# Arduino-Teensy-v44_PLUS_ESP-12E_4LAYER.net
KiCad netlist of a schematic drawn in EAGLE
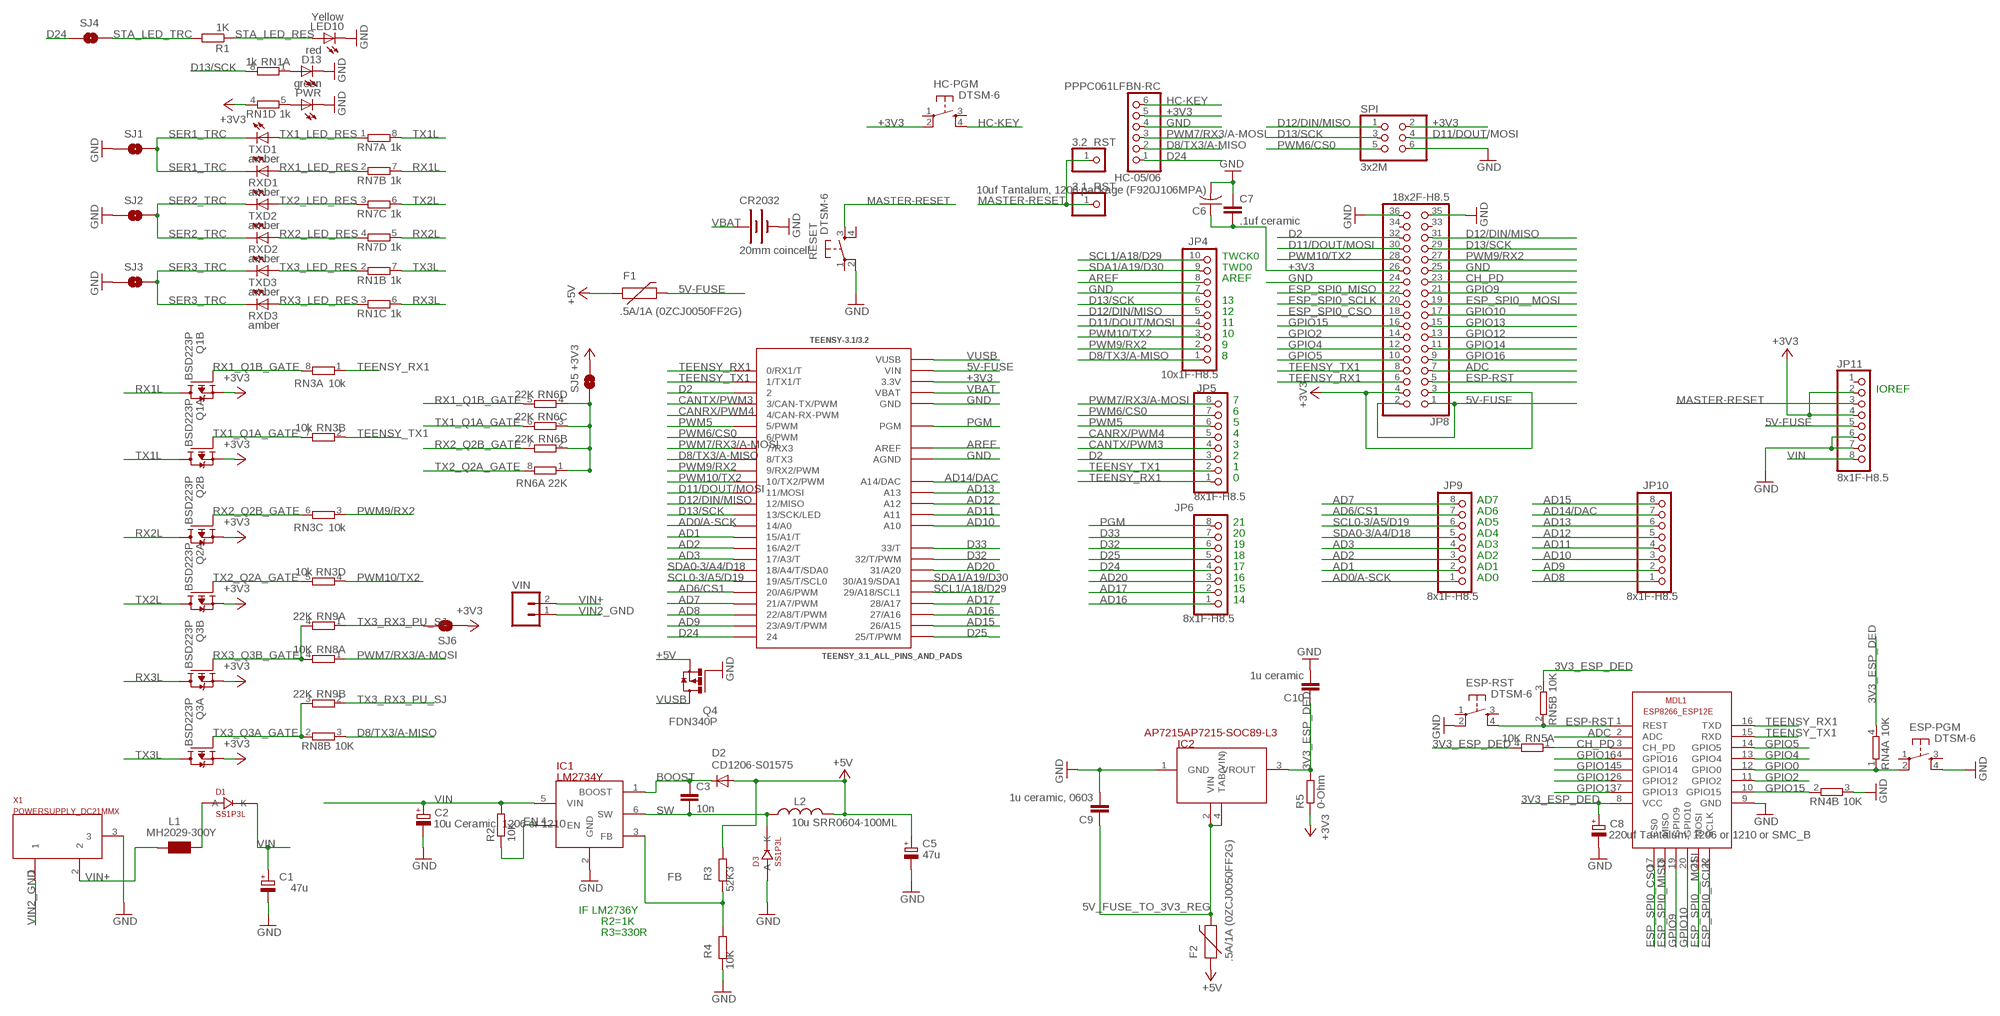
[diagram p0: schematic, sheet 1]

(export (version "E")
  (design (tool "Eeschema 10.0.6"))
  (components
    (comp (ref "3.1_RST")
      (value "PINHD-1X1CB")
      (footprint "eagle-import:1X01-CLEANBIG")
      (libsource (lib "eagle-import") (part "PINHD-1X1CB"))
    )
    (comp (ref "3.2_RST")
      (value "PINHD-1X1CB")
      (footprint "eagle-import:1X01-CLEANBIG")
      (libsource (lib "eagle-import") (part "PINHD-1X1CB"))
    )
    (comp (ref "C1")
      (value "47u")
      (footprint "eagle-import:PANASONIC_D")
      (libsource (lib "eagle-import") (part "CPOL-EUD"))
    )
    (comp (ref "C2")
      (value "10u Ceramic, 1206 or 1210")
      (footprint "eagle-import:SMC_B")
      (libsource (lib "eagle-import") (part "CPOL-EUSMCB"))
    )
    (comp (ref "C3")
      (value "10n")
      (footprint "eagle-import:C0603-ROUND")
      (libsource (lib "eagle-import") (part "C-EUC0603"))
    )
    (comp (ref "C5")
      (value "47u")
      (footprint "eagle-import:PANASONIC_D")
      (libsource (lib "eagle-import") (part "CPOL-EUD"))
    )
    (comp (ref "C6")
      (value "10uf Tantalum, 1206 package (F920J106MPA)")
      (footprint "eagle-import:C0805")
      (libsource (lib "eagle-import") (part "C-USC0805"))
    )
    (comp (ref "C7")
      (value ".1uf ceramic")
      (footprint "eagle-import:C0603-ROUND")
      (libsource (lib "eagle-import") (part "C-EUC0603"))
    )
    (comp (ref "C8")
      (value "220uf Tantalum, 1206 or 1210 or SMC_B")
      (footprint "eagle-import:SMC_B")
      (libsource (lib "eagle-import") (part "CPOL-EUSMCB"))
    )
    (comp (ref "C9")
      (value "1u ceramic, 0603")
      (footprint "eagle-import:C0603-ROUND")
      (libsource (lib "eagle-import") (part "C-EUC0603"))
    )
    (comp (ref "C10")
      (value "1u ceramic")
      (footprint "eagle-import:C0603-ROUND")
      (libsource (lib "eagle-import") (part "C-EUC0603"))
    )
    (comp (ref "CR2032")
      (value "20mm coincell")
      (footprint "eagle-import:BATTCON_20MM_4LEGS")
      (libsource (lib "eagle-import") (part "BATTERY20MM_4LEGS"))
    )
    (comp (ref "D1")
      (value "SS1P3L")
      (footprint "eagle-import:DO220AAL")
      (libsource (lib "eagle-import") (part "SS1P3L"))
    )
    (comp (ref "D2")
      (value "CD1206-S01575")
      (footprint "eagle-import:MINIMELF")
      (libsource (lib "eagle-import") (part "DIODE-MINIMELF"))
    )
    (comp (ref "D3")
      (value "SS1P3L")
      (footprint "eagle-import:DO220AAL")
      (libsource (lib "eagle-import") (part "SS1P3L"))
    )
    (comp (ref "D13")
      (value "red")
      (footprint "eagle-import:CHIPLED_0805")
      (libsource (lib "eagle-import") (part "LEDCHIPLED_0805"))
    )
    (comp (ref "ESP-PGM")
      (value "DTSM-6")
      (footprint "eagle-import:DTSM-6")
      (libsource (lib "eagle-import") (part "DTSM-6"))
    )
    (comp (ref "ESP-RST")
      (value "DTSM-6")
      (footprint "eagle-import:DTSM-6")
      (libsource (lib "eagle-import") (part "DTSM-6"))
    )
    (comp (ref "F1")
      (value ".5A/1A (0ZCJ0050FF2G)")
      (footprint "eagle-import:PTC-1206")
      (libsource (lib "eagle-import") (part "PTCSMD"))
    )
    (comp (ref "F2")
      (value ".5A/1A (0ZCJ0050FF2G)")
      (footprint "eagle-import:PTC-1206")
      (libsource (lib "eagle-import") (part "PTCSMD"))
    )
    (comp (ref "HC-05/06")
      (value "PPPC061LFBN-RC")
      (footprint "eagle-import:1X06")
      (libsource (lib "eagle-import") (part "PINHD-1X6"))
    )
    (comp (ref "HC-PGM")
      (value "DTSM-6")
      (footprint "eagle-import:DTSM-6")
      (libsource (lib "eagle-import") (part "DTSM-6"))
    )
    (comp (ref "IC1")
      (value "LM2734Y")
      (footprint "eagle-import:SOT23-6")
      (libsource (lib "eagle-import") (part "LM2736Y"))
    )
    (comp (ref "IC2")
      (value "AP7215AP7215-SOC89-L3")
      (footprint "eagle-import:SOC89-L3")
      (libsource (lib "eagle-import") (part "AP7215AP7215-SOC89-L3"))
    )
    (comp (ref "JP4")
      (value "10x1F-H8.5")
      (footprint "eagle-import:1X10")
      (libsource (lib "eagle-import") (part "PINHD-1X10"))
    )
    (comp (ref "JP5")
      (value "8x1F-H8.5")
      (footprint "eagle-import:1X08")
      (libsource (lib "eagle-import") (part "PINHD-1X8"))
    )
    (comp (ref "JP6")
      (value "8x1F-H8.5")
      (footprint "eagle-import:1X08")
      (libsource (lib "eagle-import") (part "PINHD-1X8"))
    )
    (comp (ref "JP8")
      (value "18x2F-H8.5")
      (footprint "eagle-import:2X18")
      (libsource (lib "eagle-import") (part "PINHD-2X18"))
    )
    (comp (ref "JP9")
      (value "8x1F-H8.5")
      (footprint "eagle-import:1X08")
      (libsource (lib "eagle-import") (part "PINHD-1X8"))
    )
    (comp (ref "JP10")
      (value "8x1F-H8.5")
      (footprint "eagle-import:1X08")
      (libsource (lib "eagle-import") (part "PINHD-1X8"))
    )
    (comp (ref "JP11")
      (value "8x1F-H8.5")
      (footprint "eagle-import:1X08")
      (libsource (lib "eagle-import") (part "PINHD-1X8"))
    )
    (comp (ref "L1")
      (value "MH2029-300Y")
      (footprint "eagle-import:0805")
      (libsource (lib "eagle-import") (part "WE-CBF_0805"))
    )
    (comp (ref "L2")
      (value "10u SRR0604-100ML")
      (footprint "eagle-import:SRR0604")
      (libsource (lib "eagle-import") (part "L-USSRR0604"))
    )
    (comp (ref "LED10")
      (value "Yellow")
      (footprint "eagle-import:CHIPLED_0805")
      (libsource (lib "eagle-import") (part "LEDCHIPLED_0805"))
    )
    (comp (ref "MDL1")
      (value "ESP8266-12E)")
      (footprint "eagle-import:ESP8266-ESP12E")
      (libsource (lib "eagle-import") (part "ESP8266-12EESP8266-ESP12E"))
    )
    (comp (ref "PWR")
      (value "green")
      (footprint "eagle-import:CHIPLED_0805")
      (libsource (lib "eagle-import") (part "LEDCHIPLED_0805"))
    )
    (comp (ref "Q1")
      (value "BSD223P")
      (footprint "eagle-import:SOT363_INFINEON")
      (libsource (lib "eagle-import") (part "BSD223P"))
    )
    (comp (ref "Q2")
      (value "BSD223P")
      (footprint "eagle-import:SOT363_INFINEON")
      (libsource (lib "eagle-import") (part "BSD223P"))
    )
    (comp (ref "Q3")
      (value "BSD223P")
      (footprint "eagle-import:SOT363_INFINEON")
      (libsource (lib "eagle-import") (part "BSD223P"))
    )
    (comp (ref "Q4")
      (value "FDN340P")
      (footprint "eagle-import:SUPER-SOT3")
      (libsource (lib "eagle-import") (part "FDN360P"))
    )
    (comp (ref "R1")
      (value "1K")
      (footprint "eagle-import:R0603")
      (libsource (lib "eagle-import") (part "rcl_R-EU_R0603"))
    )
    (comp (ref "R2")
      (value "10K")
      (footprint "eagle-import:R0603")
      (libsource (lib "eagle-import") (part "rcl_R-EU_R0603"))
    )
    (comp (ref "R3")
      (value "52K3")
      (footprint "eagle-import:R0603-ROUND")
      (libsource (lib "eagle-import") (part "R-EU_0603-RND"))
    )
    (comp (ref "R4")
      (value "10K")
      (footprint "eagle-import:R0603-ROUND")
      (libsource (lib "eagle-import") (part "R-EU_0603-RND"))
    )
    (comp (ref "R5")
      (value "0-Ohm")
      (footprint "eagle-import:R0603")
      (libsource (lib "eagle-import") (part "rcl_R-EU_R0603"))
    )
    (comp (ref "RESET")
      (value "DTSM-6")
      (footprint "eagle-import:DTSM-6")
      (libsource (lib "eagle-import") (part "DTSM-6"))
    )
    (comp (ref "RN1")
      (value "1k")
      (footprint "eagle-import:CAT16")
      (libsource (lib "eagle-import") (part "4R-NCAT16"))
    )
    (comp (ref "RN3")
      (value "10k")
      (footprint "eagle-import:CAT16")
      (libsource (lib "eagle-import") (part "4R-NCAT16"))
    )
    (comp (ref "RN4")
      (value "10K")
      (footprint "eagle-import:EXB34V")
      (libsource (lib "eagle-import") (part "2R-NEXB34V"))
    )
    (comp (ref "RN5")
      (value "10K")
      (footprint "eagle-import:EXB34V")
      (libsource (lib "eagle-import") (part "2R-NEXB34V"))
    )
    (comp (ref "RN6")
      (value "22K")
      (footprint "eagle-import:CAT16")
      (libsource (lib "eagle-import") (part "4R-NCAT16"))
    )
    (comp (ref "RN7")
      (value "1k")
      (footprint "eagle-import:CAT16")
      (libsource (lib "eagle-import") (part "4R-NCAT16"))
    )
    (comp (ref "RN8")
      (value "10K")
      (footprint "eagle-import:EXB34V")
      (libsource (lib "eagle-import") (part "2R-NEXB34V"))
    )
    (comp (ref "RN9")
      (value "22K")
      (footprint "eagle-import:EXB34V")
      (libsource (lib "eagle-import") (part "2R-NEXB34V"))
    )
    (comp (ref "RXD1")
      (value "amber")
      (footprint "eagle-import:CHIPLED_0805")
      (libsource (lib "eagle-import") (part "LEDCHIPLED_0805"))
    )
    (comp (ref "RXD2")
      (value "amber")
      (footprint "eagle-import:CHIPLED_0805")
      (libsource (lib "eagle-import") (part "LEDCHIPLED_0805"))
    )
    (comp (ref "RXD3")
      (value "amber")
      (footprint "eagle-import:CHIPLED_0805")
      (libsource (lib "eagle-import") (part "LEDCHIPLED_0805"))
    )
    (comp (ref "SJ1")
      (value "SOLDERJUMPERTRACE")
      (footprint "eagle-import:SJ_2S-TRACE")
      (libsource (lib "eagle-import") (part "SOLDERJUMPERTRACE"))
    )
    (comp (ref "SJ2")
      (value "SOLDERJUMPERTRACE")
      (footprint "eagle-import:SJ_2S-TRACE")
      (libsource (lib "eagle-import") (part "SOLDERJUMPERTRACE"))
    )
    (comp (ref "SJ3")
      (value "SOLDERJUMPERTRACE")
      (footprint "eagle-import:SJ_2S-TRACE")
      (libsource (lib "eagle-import") (part "SOLDERJUMPERTRACE"))
    )
    (comp (ref "SJ4")
      (value "SOLDERJUMPERTRACE")
      (footprint "eagle-import:SJ_2S-TRACE")
      (libsource (lib "eagle-import") (part "SOLDERJUMPERTRACE"))
    )
    (comp (ref "SJ5")
      (value "SOLDERJUMPERTRACE")
      (footprint "eagle-import:SJ_2S-TRACE")
      (libsource (lib "eagle-import") (part "SOLDERJUMPERTRACE"))
    )
    (comp (ref "SJ6")
      (value "SOLDERJUMPERTRACE")
      (footprint "eagle-import:SJ_2S-TRACE")
      (libsource (lib "eagle-import") (part "SOLDERJUMPERTRACE"))
    )
    (comp (ref "SPI")
      (value "3x2M")
      (footprint "eagle-import:2X03")
      (libsource (lib "eagle-import") (part "PINHD-2X3"))
    )
    (comp (ref "TEENSY-3.1/3.2")
      (value "TEENSY_3.1_ALL_PINS_AND_PADS")
      (footprint "eagle-import:TEENSY3_ALL_PINS_&_PADS")
      (libsource (lib "eagle-import") (part "TEENSY_3.1_ALL_PINS_AND_PADS"))
    )
    (comp (ref "TXD1")
      (value "amber")
      (footprint "eagle-import:CHIPLED_0805")
      (libsource (lib "eagle-import") (part "LEDCHIPLED_0805"))
    )
    (comp (ref "TXD2")
      (value "amber")
      (footprint "eagle-import:CHIPLED_0805")
      (libsource (lib "eagle-import") (part "LEDCHIPLED_0805"))
    )
    (comp (ref "TXD3")
      (value "amber")
      (footprint "eagle-import:CHIPLED_0805")
      (libsource (lib "eagle-import") (part "LEDCHIPLED_0805"))
    )
    (comp (ref "VIN")
      (value "M02LOCK_LONGPADS")
      (footprint "eagle-import:1X02_LOCK_LONGPADS")
      (libsource (lib "eagle-import") (part "M02LOCK_LONGPADS"))
    )
    (comp (ref "X1")
      (value "POWERSUPPLY_DC21MMX")
      (footprint "eagle-import:POWERSUPPLY_DC-21MM")
      (libsource (lib "eagle-import") (part "POWERSUPPLY_DC21MMX"))
    )
  )
  (nets
    (net (code "1") (name "+3V3") (class "Default")
      (node (ref "C6") (pin "1") (pinfunction "1_1") (pintype "passive"))
      (node (ref "C7") (pin "2") (pinfunction "2_2") (pintype "passive"))
      (node (ref "HC-05/06") (pin "5") (pinfunction "5_5") (pintype "passive"))
      (node (ref "HC-PGM") (pin "2") (pinfunction "2_2") (pintype "passive"))
      (node (ref "JP11") (pin "2") (pinfunction "2_2") (pintype "passive"))
      (node (ref "JP11") (pin "4") (pinfunction "4_4") (pintype "passive"))
      (node (ref "JP8") (pin "26") (pinfunction "26_26") (pintype "passive"))
      (node (ref "JP8") (pin "3") (pinfunction "3_3") (pintype "passive"))
      (node (ref "JP8") (pin "4") (pinfunction "4_4") (pintype "passive"))
      (node (ref "Q1") (pin "1") (pinfunction "S_1") (pintype "passive"))
      (node (ref "Q1") (pin "4") (pinfunction "S_4") (pintype "passive"))
      (node (ref "Q2") (pin "1") (pinfunction "S_1") (pintype "passive"))
      (node (ref "Q2") (pin "4") (pinfunction "S_4") (pintype "passive"))
      (node (ref "Q3") (pin "1") (pinfunction "S_1") (pintype "passive"))
      (node (ref "Q3") (pin "4") (pinfunction "S_4") (pintype "passive"))
      (node (ref "R5") (pin "1") (pinfunction "1_1") (pintype "passive"))
      (node (ref "RN1") (pin "4") (pinfunction "1_4") (pintype "passive"))
      (node (ref "SJ5") (pin "2") (pinfunction "2_2") (pintype "passive"))
      (node (ref "SJ6") (pin "1") (pinfunction "1_1") (pintype "passive"))
      (node (ref "SPI") (pin "2") (pinfunction "2_2") (pintype "passive"))
      (node (ref "TEENSY-3.1/3.2") (pin "3.3V") (pinfunction "3.3V_3.3V") (pintype "power_in"))
      (node (ref "TEENSY-3.1/3.2") (pin "3.3V1") (pinfunction "3.3V_3.3V1") (pintype "power_in"))
      (node (ref "TEENSY-3.1/3.2") (pin "3.3V2") (pinfunction "3.3V_3.3V2") (pintype "power_in"))
    )
    (net (code "2") (name "+5V") (class "Default")
      (node (ref "C5") (pin "+") (pinfunction "+_+") (pintype "passive"))
      (node (ref "D2") (pin "A") (pinfunction "A_A") (pintype "passive"))
      (node (ref "F1") (pin "1") (pinfunction "1_1") (pintype "bidirectional"))
      (node (ref "F2") (pin "1") (pinfunction "1_1") (pintype "bidirectional"))
      (node (ref "L2") (pin "P$2") (pinfunction "2_P$2") (pintype "passive"))
      (node (ref "Q4") (pin "2") (pinfunction "S_2") (pintype "passive"))
      (node (ref "R3") (pin "1") (pinfunction "1_1") (pintype "passive"))
    )
    (net (code "3") (name "/3V3_ESP_DED") (class "Default")
      (node (ref "C10") (pin "1") (pinfunction "1_1") (pintype "passive"))
      (node (ref "C8") (pin "+") (pinfunction "+_+") (pintype "passive"))
      (node (ref "IC2") (pin "3") (pinfunction "VROUT_3") (pintype "output"))
      (node (ref "MDL1") (pin "8") (pinfunction "VCC_8") (pintype "bidirectional"))
      (node (ref "R5") (pin "2") (pinfunction "2_2") (pintype "passive"))
      (node (ref "RN4") (pin "4") (pinfunction "2_4") (pintype "passive"))
      (node (ref "RN5") (pin "3") (pinfunction "2_3") (pintype "passive"))
      (node (ref "RN5") (pin "4") (pinfunction "2_4") (pintype "passive"))
    )
    (net (code "4") (name "/5V-FUSE") (class "Default")
      (node (ref "F1") (pin "2") (pinfunction "2_2") (pintype "bidirectional"))
      (node (ref "JP11") (pin "5") (pinfunction "5_5") (pintype "passive"))
      (node (ref "JP8") (pin "1") (pinfunction "1_1") (pintype "passive"))
      (node (ref "JP8") (pin "2") (pinfunction "2_2") (pintype "passive"))
      (node (ref "TEENSY-3.1/3.2") (pin "VIN") (pinfunction "VIN_VIN") (pintype "power_in"))
    )
    (net (code "5") (name "/5V_FUSE_TO_3V3_REG") (class "Default")
      (node (ref "C9") (pin "1") (pinfunction "1_1") (pintype "passive"))
      (node (ref "F2") (pin "2") (pinfunction "2_2") (pintype "bidirectional"))
      (node (ref "IC2") (pin "2") (pinfunction "VIN_2") (pintype "input"))
      (node (ref "IC2") (pin "4") (pinfunction "TAB(VIN)_4") (pintype "input"))
    )
    (net (code "6") (name "/AD0{slash}A-SCK") (class "Default")
      (node (ref "JP9") (pin "1") (pinfunction "1_1") (pintype "passive"))
      (node (ref "TEENSY-3.1/3.2") (pin "14/A0") (pinfunction "14/A0_14/A0") (pintype "bidirectional"))
    )
    (net (code "7") (name "/AD1") (class "Default")
      (node (ref "JP9") (pin "2") (pinfunction "2_2") (pintype "passive"))
      (node (ref "TEENSY-3.1/3.2") (pin "15/A1") (pinfunction "15/A1/T_15/A1") (pintype "bidirectional"))
    )
    (net (code "8") (name "/AD2") (class "Default")
      (node (ref "JP9") (pin "3") (pinfunction "3_3") (pintype "passive"))
      (node (ref "TEENSY-3.1/3.2") (pin "16/A2") (pinfunction "16/A2/T_16/A2") (pintype "bidirectional"))
    )
    (net (code "9") (name "/AD3") (class "Default")
      (node (ref "JP9") (pin "4") (pinfunction "4_4") (pintype "passive"))
      (node (ref "TEENSY-3.1/3.2") (pin "17/A3") (pinfunction "17/A3/T_17/A3") (pintype "bidirectional"))
    )
    (net (code "10") (name "/AD6{slash}CS1") (class "Default")
      (node (ref "JP9") (pin "7") (pinfunction "7_7") (pintype "passive"))
      (node (ref "TEENSY-3.1/3.2") (pin "20/A6") (pinfunction "20/A6/PWM_20/A6") (pintype "bidirectional"))
    )
    (net (code "11") (name "/AD7") (class "Default")
      (node (ref "JP9") (pin "8") (pinfunction "8_8") (pintype "passive"))
      (node (ref "TEENSY-3.1/3.2") (pin "21/A7") (pinfunction "21/A7/PWM_21/A7") (pintype "bidirectional"))
    )
    (net (code "12") (name "/AD8") (class "Default")
      (node (ref "JP10") (pin "1") (pinfunction "1_1") (pintype "passive"))
      (node (ref "TEENSY-3.1/3.2") (pin "22/A8") (pinfunction "22/A8/T/PWM_22/A8") (pintype "bidirectional"))
    )
    (net (code "13") (name "/AD9") (class "Default")
      (node (ref "JP10") (pin "2") (pinfunction "2_2") (pintype "passive"))
      (node (ref "TEENSY-3.1/3.2") (pin "23/A9") (pinfunction "23/A9/T/PWM_23/A9") (pintype "bidirectional"))
    )
    (net (code "14") (name "/AD10") (class "Default")
      (node (ref "JP10") (pin "3") (pinfunction "3_3") (pintype "passive"))
      (node (ref "TEENSY-3.1/3.2") (pin "A10") (pinfunction "A10_A10") (pintype "bidirectional"))
    )
    (net (code "15") (name "/AD11") (class "Default")
      (node (ref "JP10") (pin "4") (pinfunction "4_4") (pintype "passive"))
      (node (ref "TEENSY-3.1/3.2") (pin "A11") (pinfunction "A11_A11") (pintype "bidirectional"))
    )
    (net (code "16") (name "/AD12") (class "Default")
      (node (ref "JP10") (pin "5") (pinfunction "5_5") (pintype "passive"))
      (node (ref "TEENSY-3.1/3.2") (pin "A12") (pinfunction "A12_A12") (pintype "bidirectional"))
    )
    (net (code "17") (name "/AD13") (class "Default")
      (node (ref "JP10") (pin "6") (pinfunction "6_6") (pintype "passive"))
      (node (ref "TEENSY-3.1/3.2") (pin "A13") (pinfunction "A13_A13") (pintype "bidirectional"))
    )
    (net (code "18") (name "/AD14{slash}DAC") (class "Default")
      (node (ref "JP10") (pin "7") (pinfunction "7_7") (pintype "passive"))
      (node (ref "TEENSY-3.1/3.2") (pin "RESET/DAC") (pinfunction "A14/DAC_RESET/DAC") (pintype "bidirectional"))
    )
    (net (code "19") (name "/AD15") (class "Default")
      (node (ref "JP10") (pin "8") (pinfunction "8_8") (pintype "passive"))
      (node (ref "TEENSY-3.1/3.2") (pin "26") (pinfunction "26/A15_26") (pintype "bidirectional"))
    )
    (net (code "20") (name "/AD16") (class "Default")
      (node (ref "JP6") (pin "1") (pinfunction "1_1") (pintype "passive"))
      (node (ref "TEENSY-3.1/3.2") (pin "27") (pinfunction "27/A16_27") (pintype "bidirectional"))
    )
    (net (code "21") (name "/AD17") (class "Default")
      (node (ref "JP6") (pin "2") (pinfunction "2_2") (pintype "passive"))
      (node (ref "TEENSY-3.1/3.2") (pin "28") (pinfunction "28/A17_28") (pintype "bidirectional"))
    )
    (net (code "22") (name "/AD20") (class "Default")
      (node (ref "JP6") (pin "3") (pinfunction "3_3") (pintype "passive"))
      (node (ref "TEENSY-3.1/3.2") (pin "31") (pinfunction "31/A20_31") (pintype "bidirectional"))
    )
    (net (code "23") (name "/ADC") (class "Default")
      (node (ref "JP8") (pin "7") (pinfunction "7_7") (pintype "passive"))
      (node (ref "MDL1") (pin "2") (pinfunction "ADC_2") (pintype "bidirectional"))
    )
    (net (code "24") (name "/AREF") (class "Default")
      (node (ref "JP4") (pin "8") (pinfunction "8_8") (pintype "passive"))
      (node (ref "TEENSY-3.1/3.2") (pin "AREF") (pinfunction "AREF_AREF") (pintype "power_in"))
    )
    (net (code "25") (name "/BOOST") (class "Default")
      (node (ref "C3") (pin "1") (pinfunction "1_1") (pintype "passive"))
      (node (ref "D2") (pin "C") (pinfunction "C_C") (pintype "passive"))
      (node (ref "IC1") (pin "1") (pinfunction "BOOST_1") (pintype "input"))
    )
    (net (code "26") (name "/CANRX{slash}PWM4") (class "Default")
      (node (ref "JP5") (pin "5") (pinfunction "5_5") (pintype "passive"))
      (node (ref "TEENSY-3.1/3.2") (pin "4") (pinfunction "4/CAN-RX-PWM_4") (pintype "bidirectional"))
    )
    (net (code "27") (name "/CANTX{slash}PWM3") (class "Default")
      (node (ref "JP5") (pin "4") (pinfunction "4_4") (pintype "passive"))
      (node (ref "TEENSY-3.1/3.2") (pin "3") (pinfunction "3/CAN-TX/PWM_3") (pintype "bidirectional"))
    )
    (net (code "28") (name "/CH_PD") (class "Default")
      (node (ref "JP8") (pin "23") (pinfunction "23_23") (pintype "passive"))
      (node (ref "MDL1") (pin "3") (pinfunction "CH_PD_3") (pintype "bidirectional"))
      (node (ref "RN5") (pin "1") (pinfunction "1_1") (pintype "passive"))
    )
    (net (code "29") (name "/D2") (class "Default")
      (node (ref "JP5") (pin "3") (pinfunction "3_3") (pintype "passive"))
      (node (ref "JP8") (pin "32") (pinfunction "32_32") (pintype "passive"))
      (node (ref "TEENSY-3.1/3.2") (pin "2") (pinfunction "2_2") (pintype "bidirectional"))
    )
    (net (code "30") (name "/D8{slash}TX3{slash}A-MISO") (class "Default")
      (node (ref "HC-05/06") (pin "2") (pinfunction "2_2") (pintype "passive"))
      (node (ref "JP4") (pin "1") (pinfunction "1_1") (pintype "passive"))
      (node (ref "RN8") (pin "3") (pinfunction "2_3") (pintype "passive"))
      (node (ref "TEENSY-3.1/3.2") (pin "8") (pinfunction "8/TX3_8") (pintype "bidirectional"))
    )
    (net (code "31") (name "/D11{slash}DOUT{slash}MOSI") (class "Default")
      (node (ref "JP4") (pin "4") (pinfunction "4_4") (pintype "passive"))
      (node (ref "JP8") (pin "30") (pinfunction "30_30") (pintype "passive"))
      (node (ref "SPI") (pin "4") (pinfunction "4_4") (pintype "passive"))
      (node (ref "TEENSY-3.1/3.2") (pin "11") (pinfunction "11/MOSI_11") (pintype "bidirectional"))
    )
    (net (code "32") (name "/D12{slash}DIN{slash}MISO") (class "Default")
      (node (ref "JP4") (pin "5") (pinfunction "5_5") (pintype "passive"))
      (node (ref "JP8") (pin "31") (pinfunction "31_31") (pintype "passive"))
      (node (ref "SPI") (pin "1") (pinfunction "1_1") (pintype "passive"))
      (node (ref "TEENSY-3.1/3.2") (pin "12") (pinfunction "12/MISO_12") (pintype "bidirectional"))
    )
    (net (code "33") (name "/D13{slash}SCK") (class "Default")
      (node (ref "JP4") (pin "6") (pinfunction "6_6") (pintype "passive"))
      (node (ref "JP8") (pin "29") (pinfunction "29_29") (pintype "passive"))
      (node (ref "RN1") (pin "8") (pinfunction "2_8") (pintype "passive"))
      (node (ref "SPI") (pin "3") (pinfunction "3_3") (pintype "passive"))
      (node (ref "TEENSY-3.1/3.2") (pin "13") (pinfunction "13/SCK/LED_13") (pintype "bidirectional"))
    )
    (net (code "34") (name "/D24") (class "Default")
      (node (ref "HC-05/06") (pin "1") (pinfunction "1_1") (pintype "passive"))
      (node (ref "JP6") (pin "4") (pinfunction "4_4") (pintype "passive"))
      (node (ref "SJ4") (pin "1") (pinfunction "1_1") (pintype "passive"))
      (node (ref "TEENSY-3.1/3.2") (pin "24") (pinfunction "24_24") (pintype "bidirectional"))
    )
    (net (code "35") (name "/D25") (class "Default")
      (node (ref "JP6") (pin "5") (pinfunction "5_5") (pintype "passive"))
      (node (ref "TEENSY-3.1/3.2") (pin "25") (pinfunction "25/T/PWM_25") (pintype "bidirectional"))
    )
    (net (code "36") (name "/D32") (class "Default")
      (node (ref "JP6") (pin "6") (pinfunction "6_6") (pintype "passive"))
      (node (ref "TEENSY-3.1/3.2") (pin "32") (pinfunction "32/T/PWM_32") (pintype "bidirectional"))
    )
    (net (code "37") (name "/D33") (class "Default")
      (node (ref "JP6") (pin "7") (pinfunction "7_7") (pintype "passive"))
      (node (ref "TEENSY-3.1/3.2") (pin "33") (pinfunction "33/T_33") (pintype "bidirectional"))
    )
    (net (code "38") (name "/EN") (class "Default")
      (node (ref "IC1") (pin "4") (pinfunction "EN_4") (pintype "input"))
      (node (ref "R2") (pin "1") (pinfunction "1_1") (pintype "passive"))
    )
    (net (code "39") (name "/ESP-RST") (class "Default")
      (node (ref "ESP-RST") (pin "4") (pinfunction "4_4") (pintype "passive"))
      (node (ref "JP8") (pin "5") (pinfunction "5_5") (pintype "passive"))
      (node (ref "MDL1") (pin "1") (pinfunction "REST_1") (pintype "bidirectional"))
      (node (ref "RN5") (pin "2") (pinfunction "1_2") (pintype "passive"))
    )
    (net (code "40") (name "/ESP_SPI0_CSO") (class "Default")
      (node (ref "JP8") (pin "18") (pinfunction "18_18") (pintype "passive"))
      (node (ref "MDL1") (pin "17") (pinfunction "CS0_17") (pintype "bidirectional"))
    )
    (net (code "41") (name "/ESP_SPI0_MISO") (class "Default")
      (node (ref "JP8") (pin "22") (pinfunction "22_22") (pintype "passive"))
      (node (ref "MDL1") (pin "18") (pinfunction "MISO_18") (pintype "bidirectional"))
    )
    (net (code "42") (name "/ESP_SPI0_SCLK") (class "Default")
      (node (ref "JP8") (pin "20") (pinfunction "20_20") (pintype "passive"))
      (node (ref "MDL1") (pin "22") (pinfunction "SCLK_22") (pintype "bidirectional"))
    )
    (net (code "43") (name "/ESP_SPI0__MOSI") (class "Default")
      (node (ref "JP8") (pin "19") (pinfunction "19_19") (pintype "passive"))
      (node (ref "MDL1") (pin "21") (pinfunction "MOSI_21") (pintype "bidirectional"))
    )
    (net (code "44") (name "/FB") (class "Default")
      (node (ref "IC1") (pin "3") (pinfunction "FB_3") (pintype "input"))
      (node (ref "R3") (pin "2") (pinfunction "2_2") (pintype "passive"))
      (node (ref "R4") (pin "1") (pinfunction "1_1") (pintype "passive"))
    )
    (net (code "45") (name "/GPIO0") (class "Default")
      (node (ref "ESP-PGM") (pin "2") (pinfunction "2_2") (pintype "passive"))
      (node (ref "MDL1") (pin "12") (pinfunction "GPIO0_12") (pintype "bidirectional"))
      (node (ref "RN4") (pin "1") (pinfunction "1_1") (pintype "passive"))
    )
    (net (code "46") (name "/GPIO2") (class "Default")
      (node (ref "JP8") (pin "14") (pinfunction "14_14") (pintype "passive"))
      (node (ref "MDL1") (pin "11") (pinfunction "GPIO2_11") (pintype "bidirectional"))
    )
    (net (code "47") (name "/GPIO4") (class "Default")
      (node (ref "JP8") (pin "12") (pinfunction "12_12") (pintype "passive"))
      (node (ref "MDL1") (pin "13") (pinfunction "GPIO4_13") (pintype "bidirectional"))
    )
    (net (code "48") (name "/GPIO5") (class "Default")
      (node (ref "JP8") (pin "10") (pinfunction "10_10") (pintype "passive"))
      (node (ref "MDL1") (pin "14") (pinfunction "GPIO5_14") (pintype "bidirectional"))
    )
    (net (code "49") (name "/GPIO9") (class "Default")
      (node (ref "JP8") (pin "21") (pinfunction "21_21") (pintype "passive"))
      (node (ref "MDL1") (pin "19") (pinfunction "GPIO9_19") (pintype "bidirectional"))
    )
    (net (code "50") (name "/GPIO10") (class "Default")
      (node (ref "JP8") (pin "17") (pinfunction "17_17") (pintype "passive"))
      (node (ref "MDL1") (pin "20") (pinfunction "GPIO10_20") (pintype "bidirectional"))
    )
    (net (code "51") (name "/GPIO12") (class "Default")
      (node (ref "JP8") (pin "13") (pinfunction "13_13") (pintype "passive"))
      (node (ref "MDL1") (pin "6") (pinfunction "GPIO12_6") (pintype "bidirectional"))
    )
    (net (code "52") (name "/GPIO13") (class "Default")
      (node (ref "JP8") (pin "15") (pinfunction "15_15") (pintype "passive"))
      (node (ref "MDL1") (pin "7") (pinfunction "GPIO13_7") (pintype "bidirectional"))
    )
    (net (code "53") (name "/GPIO14") (class "Default")
      (node (ref "JP8") (pin "11") (pinfunction "11_11") (pintype "passive"))
      (node (ref "MDL1") (pin "5") (pinfunction "GPIO14_5") (pintype "bidirectional"))
    )
    (net (code "54") (name "/GPIO15") (class "Default")
      (node (ref "JP8") (pin "16") (pinfunction "16_16") (pintype "passive"))
      (node (ref "MDL1") (pin "10") (pinfunction "GPIO15_10") (pintype "bidirectional"))
      (node (ref "RN4") (pin "2") (pinfunction "1_2") (pintype "passive"))
    )
    (net (code "55") (name "/GPIO16") (class "Default")
      (node (ref "JP8") (pin "9") (pinfunction "9_9") (pintype "passive"))
      (node (ref "MDL1") (pin "4") (pinfunction "GPIO16_4") (pintype "bidirectional"))
    )
    (net (code "56") (name "/HC-KEY") (class "Default")
      (node (ref "HC-05/06") (pin "6") (pinfunction "6_6") (pintype "passive"))
      (node (ref "HC-PGM") (pin "4") (pinfunction "4_4") (pintype "passive"))
    )
    (net (code "57") (name "/MASTER-RESET") (class "Default")
      (node (ref "3.1_RST") (pin "1") (pinfunction "1_1") (pintype "passive"))
      (node (ref "3.2_RST") (pin "1") (pinfunction "1_1") (pintype "passive"))
      (node (ref "JP11") (pin "3") (pinfunction "3_3") (pintype "passive"))
      (node (ref "RESET") (pin "3") (pinfunction "3_3") (pintype "passive"))
    )
    (net (code "58") (name "/PGM") (class "Default")
      (node (ref "JP6") (pin "8") (pinfunction "8_8") (pintype "passive"))
      (node (ref "TEENSY-3.1/3.2") (pin "PGM") (pinfunction "PGM_PGM") (pintype "bidirectional"))
    )
    (net (code "59") (name "/PWM5") (class "Default")
      (node (ref "JP5") (pin "6") (pinfunction "6_6") (pintype "passive"))
      (node (ref "TEENSY-3.1/3.2") (pin "5") (pinfunction "5/PWM_5") (pintype "bidirectional"))
    )
    (net (code "60") (name "/PWM6{slash}CS0") (class "Default")
      (node (ref "JP5") (pin "7") (pinfunction "7_7") (pintype "passive"))
      (node (ref "SPI") (pin "5") (pinfunction "5_5") (pintype "passive"))
      (node (ref "TEENSY-3.1/3.2") (pin "6") (pinfunction "6/PWM_6") (pintype "bidirectional"))
    )
    (net (code "61") (name "/PWM7{slash}RX3{slash}A-MOSI") (class "Default")
      (node (ref "HC-05/06") (pin "3") (pinfunction "3_3") (pintype "passive"))
      (node (ref "JP5") (pin "8") (pinfunction "8_8") (pintype "passive"))
      (node (ref "RN8") (pin "1") (pinfunction "1_1") (pintype "passive"))
      (node (ref "TEENSY-3.1/3.2") (pin "7") (pinfunction "7/RX3_7") (pintype "bidirectional"))
    )
    (net (code "62") (name "/PWM9{slash}RX2") (class "Default")
      (node (ref "JP4") (pin "2") (pinfunction "2_2") (pintype "passive"))
      (node (ref "JP8") (pin "27") (pinfunction "27_27") (pintype "passive"))
      (node (ref "RN3") (pin "3") (pinfunction "1_3") (pintype "passive"))
      (node (ref "TEENSY-3.1/3.2") (pin "9") (pinfunction "9/RX2/PWM_9") (pintype "bidirectional"))
    )
    (net (code "63") (name "/PWM10{slash}TX2") (class "Default")
      (node (ref "JP4") (pin "3") (pinfunction "3_3") (pintype "passive"))
      (node (ref "JP8") (pin "28") (pinfunction "28_28") (pintype "passive"))
      (node (ref "RN3") (pin "4") (pinfunction "1_4") (pintype "passive"))
      (node (ref "TEENSY-3.1/3.2") (pin "10") (pinfunction "10/TX2/PWM_10") (pintype "bidirectional"))
    )
    (net (code "64") (name "/RX1L") (class "Default")
      (node (ref "Q1") (pin "3") (pinfunction "D_3") (pintype "passive"))
      (node (ref "RN7") (pin "7") (pinfunction "2_7") (pintype "passive"))
    )
    (net (code "65") (name "/RX1_LED_RES") (class "Default")
      (node (ref "RN7") (pin "2") (pinfunction "1_2") (pintype "passive"))
      (node (ref "RXD1") (pin "A") (pinfunction "A_A") (pintype "passive"))
    )
    (net (code "66") (name "/RX1_Q1B_GATE") (class "Default")
      (node (ref "Q1") (pin "5") (pinfunction "G_5") (pintype "passive"))
      (node (ref "RN3") (pin "8") (pinfunction "2_8") (pintype "passive"))
      (node (ref "RN6") (pin "5") (pinfunction "2_5") (pintype "passive"))
    )
    (net (code "67") (name "/RX2L") (class "Default")
      (node (ref "Q2") (pin "3") (pinfunction "D_3") (pintype "passive"))
      (node (ref "RN7") (pin "5") (pinfunction "2_5") (pintype "passive"))
    )
    (net (code "68") (name "/RX2_LED_RES") (class "Default")
      (node (ref "RN7") (pin "4") (pinfunction "1_4") (pintype "passive"))
      (node (ref "RXD2") (pin "A") (pinfunction "A_A") (pintype "passive"))
    )
    (net (code "69") (name "/RX2_Q2B_GATE") (class "Default")
      (node (ref "Q2") (pin "5") (pinfunction "G_5") (pintype "passive"))
      (node (ref "RN3") (pin "6") (pinfunction "2_6") (pintype "passive"))
      (node (ref "RN6") (pin "7") (pinfunction "2_7") (pintype "passive"))
    )
    (net (code "70") (name "/RX3L") (class "Default")
      (node (ref "Q3") (pin "3") (pinfunction "D_3") (pintype "passive"))
      (node (ref "RN1") (pin "6") (pinfunction "2_6") (pintype "passive"))
    )
    (net (code "71") (name "/RX3_LED_RES") (class "Default")
      (node (ref "RN1") (pin "3") (pinfunction "1_3") (pintype "passive"))
      (node (ref "RXD3") (pin "A") (pinfunction "A_A") (pintype "passive"))
    )
    (net (code "72") (name "/RX3_Q3B_GATE") (class "Default")
      (node (ref "Q3") (pin "5") (pinfunction "G_5") (pintype "passive"))
      (node (ref "RN8") (pin "4") (pinfunction "2_4") (pintype "passive"))
      (node (ref "RN9") (pin "4") (pinfunction "2_4") (pintype "passive"))
    )
    (net (code "73") (name "/SCL0-3{slash}A5{slash}D19") (class "Default")
      (node (ref "JP9") (pin "6") (pinfunction "6_6") (pintype "passive"))
      (node (ref "TEENSY-3.1/3.2") (pin "19/A5") (pinfunction "19/A5/T/SCL0_19/A5") (pintype "bidirectional"))
    )
    (net (code "74") (name "/SCL1{slash}A18{slash}D29") (class "Default")
      (node (ref "JP4") (pin "10") (pinfunction "10_10") (pintype "passive"))
      (node (ref "TEENSY-3.1/3.2") (pin "29") (pinfunction "29/A18/SCL1_29") (pintype "bidirectional"))
    )
    (net (code "75") (name "/SDA0-3{slash}A4{slash}D18") (class "Default")
      (node (ref "JP9") (pin "5") (pinfunction "5_5") (pintype "passive"))
      (node (ref "TEENSY-3.1/3.2") (pin "18/A4") (pinfunction "18/A4/T/SDA0_18/A4") (pintype "bidirectional"))
    )
    (net (code "76") (name "/SDA1{slash}A19{slash}D30") (class "Default")
      (node (ref "JP4") (pin "9") (pinfunction "9_9") (pintype "passive"))
      (node (ref "TEENSY-3.1/3.2") (pin "30") (pinfunction "30/A19/SDA1_30") (pintype "bidirectional"))
    )
    (net (code "77") (name "/SER1_TRC") (class "Default")
      (node (ref "RXD1") (pin "C") (pinfunction "C_C") (pintype "passive"))
      (node (ref "SJ1") (pin "2") (pinfunction "2_2") (pintype "passive"))
      (node (ref "TXD1") (pin "C") (pinfunction "C_C") (pintype "passive"))
    )
    (net (code "78") (name "/SER2_TRC") (class "Default")
      (node (ref "RXD2") (pin "C") (pinfunction "C_C") (pintype "passive"))
      (node (ref "SJ2") (pin "2") (pinfunction "2_2") (pintype "passive"))
      (node (ref "TXD2") (pin "C") (pinfunction "C_C") (pintype "passive"))
    )
    (net (code "79") (name "/SER3_TRC") (class "Default")
      (node (ref "RXD3") (pin "C") (pinfunction "C_C") (pintype "passive"))
      (node (ref "SJ3") (pin "2") (pinfunction "2_2") (pintype "passive"))
      (node (ref "TXD3") (pin "C") (pinfunction "C_C") (pintype "passive"))
    )
    (net (code "80") (name "/STA_LED_RES") (class "Default")
      (node (ref "LED10") (pin "A") (pinfunction "A_A") (pintype "passive"))
      (node (ref "R1") (pin "1") (pinfunction "1_1") (pintype "passive"))
    )
    (net (code "81") (name "/STA_LED_TRC") (class "Default")
      (node (ref "R1") (pin "2") (pinfunction "2_2") (pintype "passive"))
      (node (ref "SJ4") (pin "2") (pinfunction "2_2") (pintype "passive"))
    )
    (net (code "82") (name "/SW") (class "Default")
      (node (ref "C3") (pin "2") (pinfunction "2_2") (pintype "passive"))
      (node (ref "D3") (pin "P$1") (pinfunction "K_P$1") (pintype "bidirectional"))
      (node (ref "IC1") (pin "6") (pinfunction "SW_6") (pintype "output"))
      (node (ref "L2") (pin "P$1") (pinfunction "1_P$1") (pintype "passive"))
    )
    (net (code "83") (name "/TEENSY_RX1") (class "Default")
      (node (ref "JP5") (pin "1") (pinfunction "1_1") (pintype "passive"))
      (node (ref "JP8") (pin "6") (pinfunction "6_6") (pintype "passive"))
      (node (ref "MDL1") (pin "16") (pinfunction "TXD_16") (pintype "bidirectional"))
      (node (ref "RN3") (pin "1") (pinfunction "1_1") (pintype "passive"))
      (node (ref "TEENSY-3.1/3.2") (pin "0") (pinfunction "0/RX1/T_0") (pintype "bidirectional"))
    )
    (net (code "84") (name "/TEENSY_TX1") (class "Default")
      (node (ref "JP5") (pin "2") (pinfunction "2_2") (pintype "passive"))
      (node (ref "JP8") (pin "8") (pinfunction "8_8") (pintype "passive"))
      (node (ref "MDL1") (pin "15") (pinfunction "RXD_15") (pintype "bidirectional"))
      (node (ref "RN3") (pin "2") (pinfunction "1_2") (pintype "passive"))
      (node (ref "TEENSY-3.1/3.2") (pin "1") (pinfunction "1/TX1/T_1") (pintype "bidirectional"))
    )
    (net (code "85") (name "/TX1L") (class "Default")
      (node (ref "Q1") (pin "6") (pinfunction "D_6") (pintype "passive"))
      (node (ref "RN7") (pin "8") (pinfunction "2_8") (pintype "passive"))
    )
    (net (code "86") (name "/TX1_LED_RES") (class "Default")
      (node (ref "RN7") (pin "1") (pinfunction "1_1") (pintype "passive"))
      (node (ref "TXD1") (pin "A") (pinfunction "A_A") (pintype "passive"))
    )
    (net (code "87") (name "/TX1_Q1A_GATE") (class "Default")
      (node (ref "Q1") (pin "2") (pinfunction "G_2") (pintype "passive"))
      (node (ref "RN3") (pin "7") (pinfunction "2_7") (pintype "passive"))
      (node (ref "RN6") (pin "6") (pinfunction "2_6") (pintype "passive"))
    )
    (net (code "88") (name "/TX2L") (class "Default")
      (node (ref "Q2") (pin "6") (pinfunction "D_6") (pintype "passive"))
      (node (ref "RN7") (pin "6") (pinfunction "2_6") (pintype "passive"))
    )
    (net (code "89") (name "/TX2_LED_RES") (class "Default")
      (node (ref "RN7") (pin "3") (pinfunction "1_3") (pintype "passive"))
      (node (ref "TXD2") (pin "A") (pinfunction "A_A") (pintype "passive"))
    )
    (net (code "90") (name "/TX2_Q2A_GATE") (class "Default")
      (node (ref "Q2") (pin "2") (pinfunction "G_2") (pintype "passive"))
      (node (ref "RN3") (pin "5") (pinfunction "2_5") (pintype "passive"))
      (node (ref "RN6") (pin "8") (pinfunction "2_8") (pintype "passive"))
    )
    (net (code "91") (name "/TX3L") (class "Default")
      (node (ref "Q3") (pin "6") (pinfunction "D_6") (pintype "passive"))
      (node (ref "RN1") (pin "7") (pinfunction "2_7") (pintype "passive"))
    )
    (net (code "92") (name "/TX3_LED_RES") (class "Default")
      (node (ref "RN1") (pin "2") (pinfunction "1_2") (pintype "passive"))
      (node (ref "TXD3") (pin "A") (pinfunction "A_A") (pintype "passive"))
    )
    (net (code "93") (name "/TX3_Q3A_GATE") (class "Default")
      (node (ref "Q3") (pin "2") (pinfunction "G_2") (pintype "passive"))
      (node (ref "RN8") (pin "2") (pinfunction "1_2") (pintype "passive"))
      (node (ref "RN9") (pin "3") (pinfunction "2_3") (pintype "passive"))
    )
    (net (code "94") (name "/TX3_RX3_PU_SJ") (class "Default")
      (node (ref "RN9") (pin "1") (pinfunction "1_1") (pintype "passive"))
      (node (ref "RN9") (pin "2") (pinfunction "1_2") (pintype "passive"))
      (node (ref "SJ6") (pin "2") (pinfunction "2_2") (pintype "passive"))
    )
    (net (code "95") (name "/VBAT") (class "Default")
      (node (ref "CR2032") (pin "POSITIVE@1") (pinfunction "+_POSITIVE@1") (pintype "power_in"))
      (node (ref "CR2032") (pin "POSITIVE@2") (pinfunction "+_POSITIVE@2") (pintype "power_in"))
      (node (ref "CR2032") (pin "POSITIVE@3") (pinfunction "+_POSITIVE@3") (pintype "power_in"))
      (node (ref "CR2032") (pin "POSITIVE@4") (pinfunction "+_POSITIVE@4") (pintype "power_in"))
      (node (ref "TEENSY-3.1/3.2") (pin "VBAT") (pinfunction "VBAT_VBAT") (pintype "power_in"))
    )
    (net (code "96") (name "/VIN") (class "Default")
      (node (ref "C1") (pin "+") (pinfunction "+_+") (pintype "passive"))
      (node (ref "C2") (pin "+") (pinfunction "+_+") (pintype "passive"))
      (node (ref "D1") (pin "P$1") (pinfunction "K_P$1") (pintype "bidirectional"))
      (node (ref "IC1") (pin "5") (pinfunction "VIN_5") (pintype "input"))
      (node (ref "JP11") (pin "8") (pinfunction "8_8") (pintype "passive"))
      (node (ref "R2") (pin "2") (pinfunction "2_2") (pintype "passive"))
    )
    (net (code "97") (name "/VIN+") (class "Default")
      (node (ref "L1") (pin "2") (pinfunction "2_2") (pintype "passive"))
      (node (ref "VIN") (pin "2") (pinfunction "2_2") (pintype "passive"))
      (node (ref "X1") (pin "2") (pinfunction "2_2") (pintype "power_in"))
    )
    (net (code "98") (name "/VIN2_GND") (class "Default")
      (node (ref "VIN") (pin "1") (pinfunction "1_1") (pintype "passive"))
      (node (ref "X1") (pin "1") (pinfunction "1_1") (pintype "power_in"))
    )
    (net (code "99") (name "/VUSB") (class "Default")
      (node (ref "Q4") (pin "3") (pinfunction "D_3") (pintype "passive"))
      (node (ref "TEENSY-3.1/3.2") (pin "VUSB") (pinfunction "VUSB_VUSB") (pintype "power_in"))
    )
    (net (code "100") (name "GND") (class "Default")
      (node (ref "C1") (pin "-") (pinfunction "-_-") (pintype "passive"))
      (node (ref "C10") (pin "2") (pinfunction "2_2") (pintype "passive"))
      (node (ref "C2") (pin "-") (pinfunction "-_-") (pintype "passive"))
      (node (ref "C5") (pin "-") (pinfunction "-_-") (pintype "passive"))
      (node (ref "C6") (pin "2") (pinfunction "2_2") (pintype "passive"))
      (node (ref "C7") (pin "1") (pinfunction "1_1") (pintype "passive"))
      (node (ref "C8") (pin "-") (pinfunction "-_-") (pintype "passive"))
      (node (ref "C9") (pin "2") (pinfunction "2_2") (pintype "passive"))
      (node (ref "CR2032") (pin "NEGATIVE") (pinfunction "-_NEGATIVE") (pintype "power_in"))
      (node (ref "D13") (pin "C") (pinfunction "C_C") (pintype "passive"))
      (node (ref "D3") (pin "P$2") (pinfunction "A_P$2") (pintype "bidirectional"))
      (node (ref "ESP-PGM") (pin "4") (pinfunction "4_4") (pintype "passive"))
      (node (ref "ESP-RST") (pin "2") (pinfunction "2_2") (pintype "passive"))
      (node (ref "HC-05/06") (pin "4") (pinfunction "4_4") (pintype "passive"))
      (node (ref "IC1") (pin "2") (pinfunction "GND_2") (pintype "power_in"))
      (node (ref "IC2") (pin "1") (pinfunction "GND_1") (pintype "power_in"))
      (node (ref "JP11") (pin "6") (pinfunction "6_6") (pintype "passive"))
      (node (ref "JP11") (pin "7") (pinfunction "7_7") (pintype "passive"))
      (node (ref "JP4") (pin "7") (pinfunction "7_7") (pintype "passive"))
      (node (ref "JP8") (pin "24") (pinfunction "24_24") (pintype "passive"))
      (node (ref "JP8") (pin "25") (pinfunction "25_25") (pintype "passive"))
      (node (ref "JP8") (pin "35") (pinfunction "35_35") (pintype "passive"))
      (node (ref "JP8") (pin "36") (pinfunction "36_36") (pintype "passive"))
      (node (ref "LED10") (pin "C") (pinfunction "C_C") (pintype "passive"))
      (node (ref "MDL1") (pin "9") (pinfunction "GND_9") (pintype "bidirectional"))
      (node (ref "PWR") (pin "C") (pinfunction "C_C") (pintype "passive"))
      (node (ref "Q4") (pin "1") (pinfunction "G_1") (pintype "passive"))
      (node (ref "R4") (pin "2") (pinfunction "2_2") (pintype "passive"))
      (node (ref "RESET") (pin "2") (pinfunction "2_2") (pintype "passive"))
      (node (ref "RN4") (pin "3") (pinfunction "2_3") (pintype "passive"))
      (node (ref "SJ1") (pin "1") (pinfunction "1_1") (pintype "passive"))
      (node (ref "SJ2") (pin "1") (pinfunction "1_1") (pintype "passive"))
      (node (ref "SJ3") (pin "1") (pinfunction "1_1") (pintype "passive"))
      (node (ref "SPI") (pin "6") (pinfunction "6_6") (pintype "passive"))
      (node (ref "TEENSY-3.1/3.2") (pin "AGND") (pinfunction "AGND_AGND") (pintype "power_in"))
      (node (ref "TEENSY-3.1/3.2") (pin "GND") (pinfunction "GND_GND") (pintype "power_in"))
      (node (ref "TEENSY-3.1/3.2") (pin "GND1") (pinfunction "GND_GND1") (pintype "power_in"))
      (node (ref "TEENSY-3.1/3.2") (pin "GND2") (pinfunction "GND_GND2") (pintype "power_in"))
      (node (ref "X1") (pin "3") (pinfunction "3_3") (pintype "power_in"))
    )
    (net (code "101") (name "Net-(D1-A)") (class "Default")
      (node (ref "D1") (pin "P$2") (pinfunction "A_P$2") (pintype "bidirectional"))
      (node (ref "L1") (pin "1") (pinfunction "1_1") (pintype "passive"))
    )
    (net (code "102") (name "Net-(D13-PadA)") (class "Default")
      (node (ref "D13") (pin "A") (pinfunction "A_A") (pintype "passive"))
      (node (ref "RN1") (pin "1") (pinfunction "1_1") (pintype "passive"))
    )
    (net (code "103") (name "Net-(RN1D-2)") (class "Default")
      (node (ref "PWR") (pin "A") (pinfunction "A_A") (pintype "passive"))
      (node (ref "RN1") (pin "5") (pinfunction "2_5") (pintype "passive"))
    )
    (net (code "104") (name "Net-(RN6B-1)") (class "Default")
      (node (ref "RN6") (pin "1") (pinfunction "1_1") (pintype "passive"))
      (node (ref "RN6") (pin "2") (pinfunction "1_2") (pintype "passive"))
      (node (ref "RN6") (pin "3") (pinfunction "1_3") (pintype "passive"))
      (node (ref "RN6") (pin "4") (pinfunction "1_4") (pintype "passive"))
      (node (ref "SJ5") (pin "1") (pinfunction "1_1") (pintype "passive"))
    )
    (net (code "105") (name "unconnected-(ESP-PGM-Pad1)") (class "Default")
      (node (ref "ESP-PGM") (pin "1") (pinfunction "1_1") (pintype "passive"))
    )
    (net (code "106") (name "unconnected-(ESP-PGM-Pad3)") (class "Default")
      (node (ref "ESP-PGM") (pin "3") (pinfunction "3_3") (pintype "passive"))
    )
    (net (code "107") (name "unconnected-(ESP-RST-Pad1)") (class "Default")
      (node (ref "ESP-RST") (pin "1") (pinfunction "1_1") (pintype "passive"))
    )
    (net (code "108") (name "unconnected-(ESP-RST-Pad3)") (class "Default")
      (node (ref "ESP-RST") (pin "3") (pinfunction "3_3") (pintype "passive"))
    )
    (net (code "109") (name "unconnected-(HC-PGM-Pad1)") (class "Default")
      (node (ref "HC-PGM") (pin "1") (pinfunction "1_1") (pintype "passive"))
    )
    (net (code "110") (name "unconnected-(HC-PGM-Pad3)") (class "Default")
      (node (ref "HC-PGM") (pin "3") (pinfunction "3_3") (pintype "passive"))
    )
    (net (code "111") (name "unconnected-(JP8-Pad33)") (class "Default")
      (node (ref "JP8") (pin "33") (pinfunction "33_33") (pintype "passive"))
    )
    (net (code "112") (name "unconnected-(JP8-Pad34)") (class "Default")
      (node (ref "JP8") (pin "34") (pinfunction "34_34") (pintype "passive"))
    )
    (net (code "113") (name "unconnected-(JP11-Pad1)") (class "Default")
      (node (ref "JP11") (pin "1") (pinfunction "1_1") (pintype "passive"))
    )
    (net (code "114") (name "unconnected-(RESET-Pad1)") (class "Default")
      (node (ref "RESET") (pin "1") (pinfunction "1_1") (pintype "passive"))
    )
    (net (code "115") (name "unconnected-(RESET-Pad4)") (class "Default")
      (node (ref "RESET") (pin "4") (pinfunction "4_4") (pintype "passive"))
    )
  )
)
